# FPGA_USB.net
KiCad netlist of a schematic drawn in Altium Designer
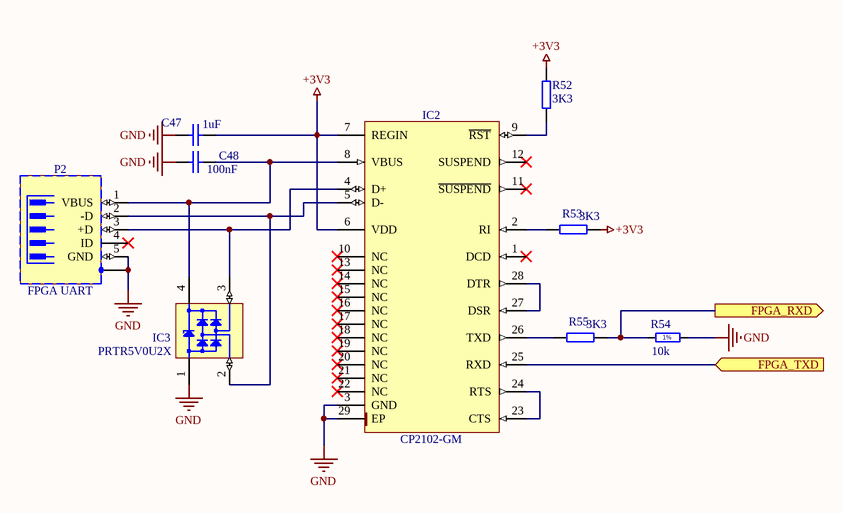
[diagram p0: FPGA_USB.SchDoc]

(export (version "E")
  (design (tool "Eeschema 10.0.6"))
  (components
    (comp (ref "C47")
      (value "1uF")
      (footprint "CC1608-0603")
      (description "Capacitor")
      (fields
        (field (name "TOLERANCE") "±10%")
        (field (name "VOLTAGE") "25V")
        (field (name "PUBLISHER") "Altium Limited")
      )
      (libsource (lib "wr_switch") (part "Cap"))
    )
    (comp (ref "C48")
      (value "100nF")
      (footprint "CAPC1608X87N")
      (description "Non-polarised capacitor")
      (fields
        (field (name "PART NUMBER") "CC0603_100NF_50V_10%_X7R")
        (field (name "VOLTAGE") "50V")
        (field (name "AUTHOR") "CERN DEM JLC")
      )
      (libsource (lib "Capacitors") (part "Capacitor - non polarized"))
    )
    (comp (ref "IC2")
      (value "CP2102-GM")
      (footprint "QFN50P500X500X100-29N-S335")
      (description "Single-Chip USB to UART Bridge")
      (fields (field (name "MANUFACTURER") "SILICON LABS") (field (name "AUTHOR") "CERN DEM JLC"))
      (libsource (lib "wr_switch") (part "CP2102-GM"))
    )
    (comp (ref "IC3")
      (value "PRTR5V0U2X")
      (footprint "SOT190P230X110-4N")
      (description "Ultra Low Capacitance Double Rail-to-Rail ESD Protection Diode")
      (fields
        (field (name "VOLTAGE") "5.5V")
        (field (name "MANUFACTURER") "PHILIPS NXP")
        (field (name "AUTHOR") "CERN DEM JLC")
      )
      (libsource (lib "wr_switch") (part "PRTR5V0U2X"))
    )
    (comp (ref "P2")
      (value "FPGA UART")
      (footprint "TYCO_1734035-1")
      (description "5 Pin + 1 Shield Mini USB Type B Receptacle")
      (fields
        (field (name "PART NUMBER") "TYCO_1734035-1")
        (field (name "MANUFACTURER") "TYCO ELECTRONICS")
        (field (name "AUTHOR") "CERN DEM JLC")
      )
      (libsource (lib "wr_switch") (part "TYCO_1734035-1"))
    )
    (comp (ref "R52")
      (value "3K3")
      (footprint "0603")
      (description "SMD Resistor")
      (fields (field (name "TOLERANCE") "±1%"))
      (libsource (lib "wr_switch") (part "RES_SMD"))
    )
    (comp (ref "R53")
      (value "3K3")
      (footprint "0603")
      (description "SMD Resistor")
      (fields (field (name "TOLERANCE") "±1%"))
      (libsource (lib "wr_switch") (part "RES_SMD"))
    )
    (comp (ref "R54")
      (value "10k")
      (footprint "RESC1608X55N")
      (description "Resistor - 1%")
      (fields
        (field (name "PART NUMBER") "R0603_10K_1%_0.1W_100PPM")
        (field (name "POWER") "0.1W")
        (field (name "AUTHOR") "CERN DEM JLC")
      )
      (libsource (lib "Resistors") (part "Resistor - 1%"))
    )
    (comp (ref "R55")
      (value "3K3")
      (footprint "0603")
      (description "SMD Resistor")
      (fields (field (name "TOLERANCE") "±1%"))
      (libsource (lib "wr_switch") (part "RES_SMD"))
    )
  )
  (nets
    (net (code "1") (name "+3V3") (class "Default")
      (node (ref "C47") (pin "2") (pinfunction "2_2") (pintype "passive"))
      (node (ref "IC2") (pin "6") (pinfunction "VDD_6") (pintype "power_in"))
      (node (ref "IC2") (pin "7") (pinfunction "REGIN_7") (pintype "power_in"))
      (node (ref "R52") (pin "2") (pinfunction "2_2") (pintype "passive"))
      (node (ref "R53") (pin "2") (pinfunction "2_2") (pintype "passive"))
    )
    (net (code "2") (name "/FPGA_RXD") (class "Default")
      (node (ref "R54") (pin "1") (pinfunction "1_1") (pintype "passive"))
      (node (ref "R55") (pin "2") (pinfunction "2_2") (pintype "passive"))
    )
    (net (code "3") (name "/FPGA_TXD") (class "Default")
      (node (ref "IC2") (pin "25") (pinfunction "RXD_25") (pintype "input"))
    )
    (net (code "4") (name "GND") (class "Default")
      (node (ref "C47") (pin "1") (pinfunction "1_1") (pintype "passive"))
      (node (ref "C48") (pin "2") (pinfunction "2_2") (pintype "passive"))
      (node (ref "IC2") (pin "29") (pinfunction "EP_29") (pintype "power_in"))
      (node (ref "IC2") (pin "3") (pinfunction "GND_3") (pintype "power_in"))
      (node (ref "IC3") (pin "1") (pinfunction "GND_1") (pintype "power_in"))
      (node (ref "P2") (pin "5") (pinfunction "GND_5") (pintype "bidirectional"))
      (node (ref "P2") (pin "6") (pinfunction "SH_6") (pintype "power_in"))
      (node (ref "R54") (pin "2") (pinfunction "2_2") (pintype "passive"))
    )
    (net (code "5") (name "Net-(IC2-CTS)") (class "Default")
      (node (ref "IC2") (pin "23") (pinfunction "CTS_23") (pintype "input"))
      (node (ref "IC2") (pin "24") (pinfunction "RTS_24") (pintype "output"))
    )
    (net (code "6") (name "Net-(IC2-D+)") (class "Default")
      (node (ref "IC2") (pin "4") (pinfunction "D+_4") (pintype "bidirectional"))
      (node (ref "IC3") (pin "3") (pinfunction "I/O2_3") (pintype "bidirectional"))
      (node (ref "P2") (pin "3") (pinfunction "+D_3") (pintype "bidirectional"))
    )
    (net (code "7") (name "Net-(IC2-D-)") (class "Default")
      (node (ref "IC2") (pin "5") (pinfunction "D-_5") (pintype "bidirectional"))
      (node (ref "IC3") (pin "2") (pinfunction "I/O1_2") (pintype "bidirectional"))
      (node (ref "P2") (pin "2") (pinfunction "-D_2") (pintype "bidirectional"))
    )
    (net (code "8") (name "Net-(IC2-DSR)") (class "Default")
      (node (ref "IC2") (pin "27") (pinfunction "DSR_27") (pintype "input"))
      (node (ref "IC2") (pin "28") (pinfunction "DTR_28") (pintype "output"))
    )
    (net (code "9") (name "Net-(IC2-RI)") (class "Default")
      (node (ref "IC2") (pin "2") (pinfunction "RI_2") (pintype "input"))
      (node (ref "R53") (pin "1") (pinfunction "1_1") (pintype "passive"))
    )
    (net (code "10") (name "Net-(IC2-TXD)") (class "Default")
      (node (ref "IC2") (pin "26") (pinfunction "TXD_26") (pintype "output"))
      (node (ref "R55") (pin "1") (pinfunction "1_1") (pintype "passive"))
    )
    (net (code "11") (name "Net-(IC2-VBUS)") (class "Default")
      (node (ref "C48") (pin "1") (pinfunction "1_1") (pintype "passive"))
      (node (ref "IC2") (pin "8") (pinfunction "VBUS_8") (pintype "input"))
      (node (ref "IC3") (pin "4") (pinfunction "VCC_4") (pintype "power_in"))
      (node (ref "P2") (pin "1") (pinfunction "VBUS_1") (pintype "bidirectional"))
    )
    (net (code "12") (name "Net-(IC2-~{RST})") (class "Default")
      (node (ref "IC2") (pin "9") (pinfunction "~{RST}_9") (pintype "bidirectional"))
      (node (ref "R52") (pin "1") (pinfunction "1_1") (pintype "passive"))
    )
    (net (code "13") (name "unconnected-(IC2-DCD-Pad1)") (class "Default")
      (node (ref "IC2") (pin "1") (pinfunction "DCD_1") (pintype "input+no_connect"))
    )
    (net (code "14") (name "unconnected-(IC2-NC-Pad10)") (class "Default")
      (node (ref "IC2") (pin "10") (pinfunction "NC_10") (pintype "passive+no_connect"))
    )
    (net (code "15") (name "unconnected-(IC2-NC-Pad13)") (class "Default")
      (node (ref "IC2") (pin "13") (pinfunction "NC_13") (pintype "passive+no_connect"))
    )
    (net (code "16") (name "unconnected-(IC2-NC-Pad14)") (class "Default")
      (node (ref "IC2") (pin "14") (pinfunction "NC_14") (pintype "passive+no_connect"))
    )
    (net (code "17") (name "unconnected-(IC2-NC-Pad15)") (class "Default")
      (node (ref "IC2") (pin "15") (pinfunction "NC_15") (pintype "passive+no_connect"))
    )
    (net (code "18") (name "unconnected-(IC2-NC-Pad16)") (class "Default")
      (node (ref "IC2") (pin "16") (pinfunction "NC_16") (pintype "passive+no_connect"))
    )
    (net (code "19") (name "unconnected-(IC2-NC-Pad17)") (class "Default")
      (node (ref "IC2") (pin "17") (pinfunction "NC_17") (pintype "passive+no_connect"))
    )
    (net (code "20") (name "unconnected-(IC2-NC-Pad18)") (class "Default")
      (node (ref "IC2") (pin "18") (pinfunction "NC_18") (pintype "passive+no_connect"))
    )
    (net (code "21") (name "unconnected-(IC2-NC-Pad19)") (class "Default")
      (node (ref "IC2") (pin "19") (pinfunction "NC_19") (pintype "passive+no_connect"))
    )
    (net (code "22") (name "unconnected-(IC2-NC-Pad20)") (class "Default")
      (node (ref "IC2") (pin "20") (pinfunction "NC_20") (pintype "passive+no_connect"))
    )
    (net (code "23") (name "unconnected-(IC2-NC-Pad21)") (class "Default")
      (node (ref "IC2") (pin "21") (pinfunction "NC_21") (pintype "passive+no_connect"))
    )
    (net (code "24") (name "unconnected-(IC2-NC-Pad22)") (class "Default")
      (node (ref "IC2") (pin "22") (pinfunction "NC_22") (pintype "passive+no_connect"))
    )
    (net (code "25") (name "unconnected-(IC2-SUSPEND-Pad12)") (class "Default")
      (node (ref "IC2") (pin "12") (pinfunction "SUSPEND_12") (pintype "output+no_connect"))
    )
    (net (code "26") (name "unconnected-(IC2-~{SUSPEND}-Pad11)") (class "Default")
      (node (ref "IC2") (pin "11") (pinfunction "~{SUSPEND}_11") (pintype "output+no_connect"))
    )
    (net (code "27") (name "unconnected-(P2-ID-Pad4)") (class "Default")
      (node (ref "P2") (pin "4") (pinfunction "ID_4") (pintype "passive+no_connect"))
    )
  )
)
